# posboard.net
KiCad netlist of a schematic drawn in EAGLE
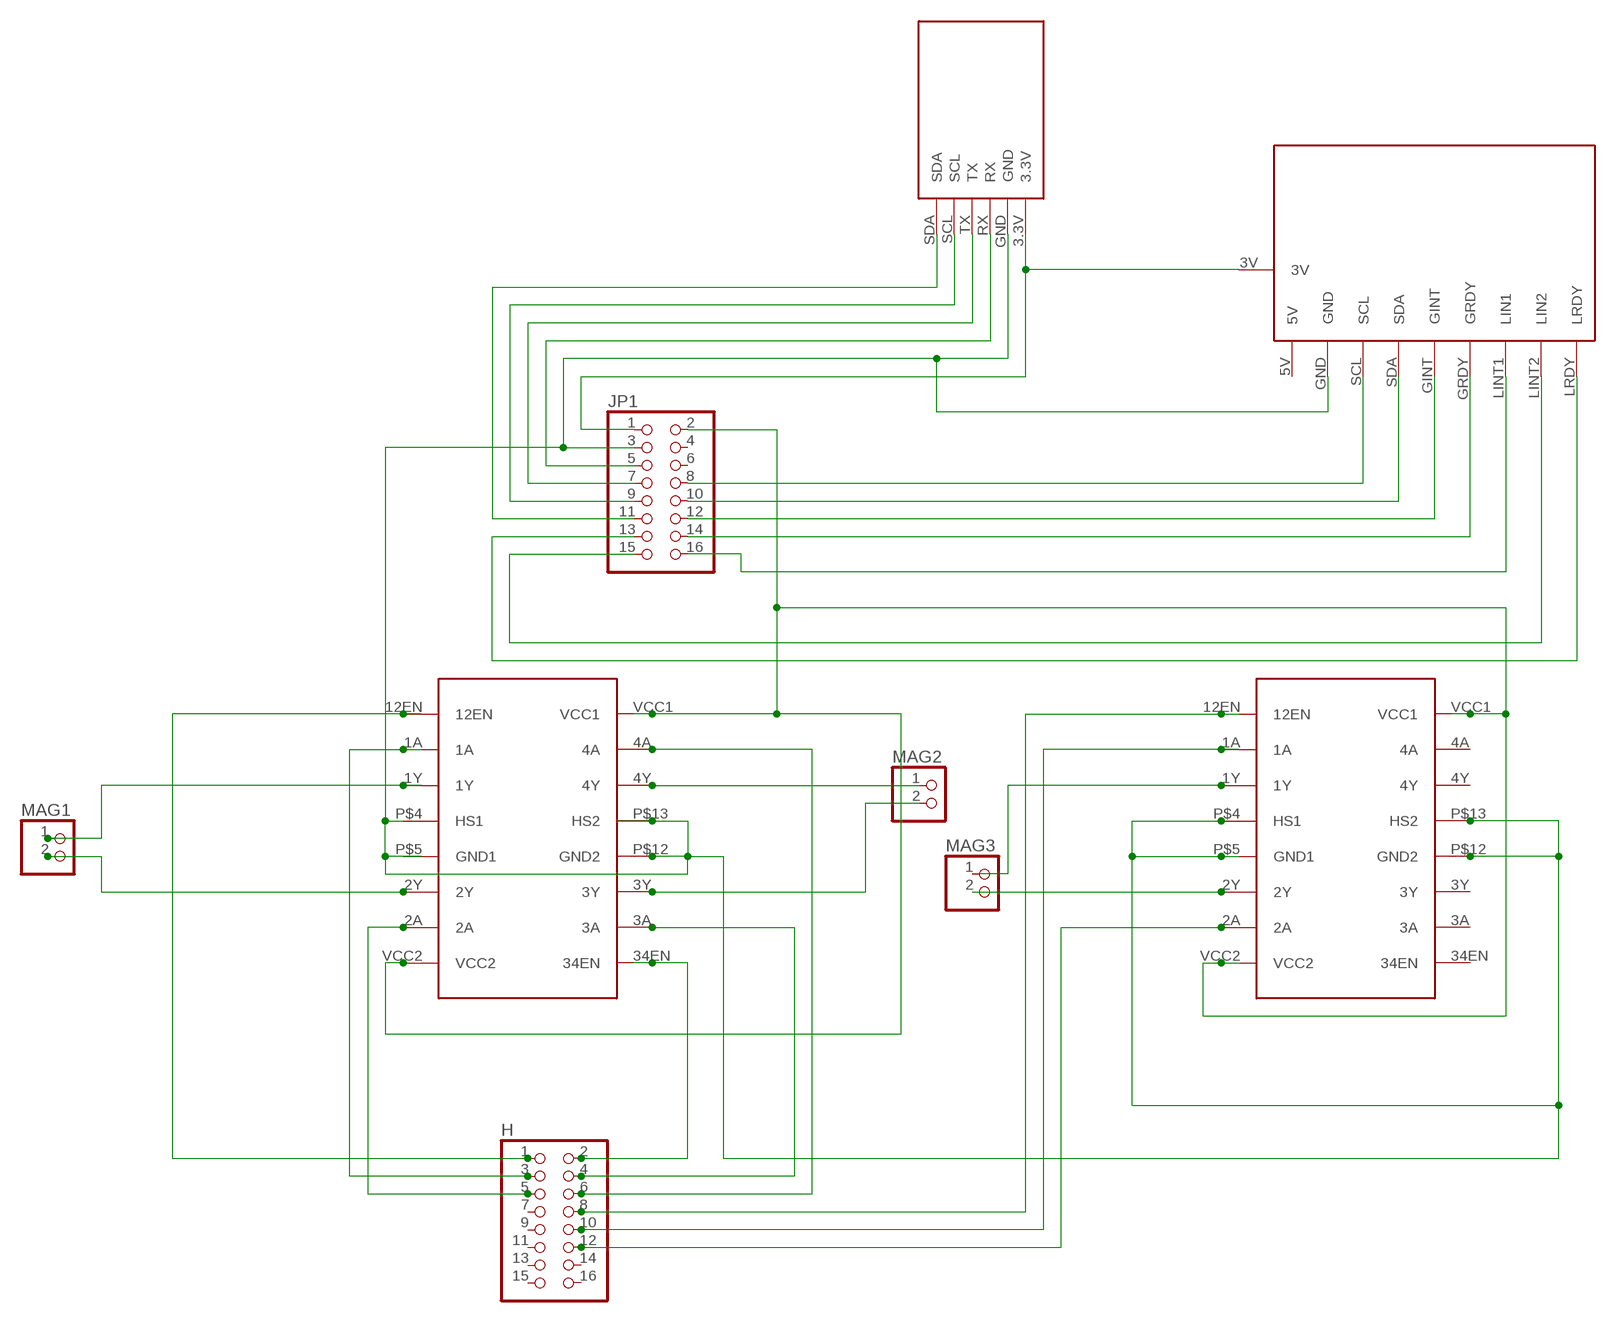
[diagram p0: schematic, sheet 1]

(export (version "E")
  (design (tool "Eeschema 10.0.6"))
  (components
    (comp (ref "H")
      (value "PINHD-2X8")
      (footprint "eagle-import:2X08")
      (libsource (lib "eagle-import") (part "PINHD-2X8"))
    )
    (comp (ref "JP1")
      (value "PINHD-2X8")
      (footprint "eagle-import:2X08")
      (libsource (lib "eagle-import") (part "PINHD-2X8"))
    )
    (comp (ref "MAG1")
      (value "PINHD-1X2")
      (footprint "eagle-import:1X02")
      (libsource (lib "eagle-import") (part "PINHD-1X2"))
    )
    (comp (ref "MAG2")
      (value "PINHD-1X2")
      (footprint "eagle-import:1X02")
      (libsource (lib "eagle-import") (part "PINHD-1X2"))
    )
    (comp (ref "MAG3")
      (value "PINHD-1X2")
      (footprint "eagle-import:1X02")
      (libsource (lib "eagle-import") (part "PINHD-1X2"))
    )
    (comp (ref "U$1")
      (value "GPS")
      (footprint "eagle-import:GPS")
      (libsource (lib "eagle-import") (part "GPS"))
    )
    (comp (ref "U$2")
      (value "IMU")
      (footprint "eagle-import:IMU")
      (libsource (lib "eagle-import") (part "IMU"))
    )
    (comp (ref "U$3")
      (value "HBRIDGE")
      (footprint "eagle-import:HBRIDGE")
      (libsource (lib "eagle-import") (part "HBRIDGE"))
    )
    (comp (ref "U$4")
      (value "HBRIDGE")
      (footprint "eagle-import:HBRIDGE")
      (libsource (lib "eagle-import") (part "HBRIDGE"))
    )
  )
  (nets
    (net (code "1") (name "Net-(H-Pad1)") (class "Default")
      (node (ref "H") (pin "1") (pinfunction "1_1") (pintype "passive"))
      (node (ref "U$3") (pin "12EN") (pinfunction "12EN_12EN") (pintype "bidirectional"))
    )
    (net (code "2") (name "Net-(H-Pad2)") (class "Default")
      (node (ref "H") (pin "2") (pinfunction "2_2") (pintype "passive"))
      (node (ref "U$3") (pin "34EN") (pinfunction "34EN_34EN") (pintype "bidirectional"))
    )
    (net (code "3") (name "Net-(H-Pad3)") (class "Default")
      (node (ref "H") (pin "3") (pinfunction "3_3") (pintype "passive"))
      (node (ref "U$3") (pin "1A") (pinfunction "1A_1A") (pintype "bidirectional"))
    )
    (net (code "4") (name "Net-(H-Pad4)") (class "Default")
      (node (ref "H") (pin "4") (pinfunction "4_4") (pintype "passive"))
      (node (ref "U$3") (pin "3A") (pinfunction "3A_3A") (pintype "bidirectional"))
    )
    (net (code "5") (name "Net-(H-Pad5)") (class "Default")
      (node (ref "H") (pin "5") (pinfunction "5_5") (pintype "passive"))
      (node (ref "U$3") (pin "2A") (pinfunction "2A_2A") (pintype "bidirectional"))
    )
    (net (code "6") (name "Net-(H-Pad6)") (class "Default")
      (node (ref "H") (pin "6") (pinfunction "6_6") (pintype "passive"))
      (node (ref "U$3") (pin "4A") (pinfunction "4A_4A") (pintype "bidirectional"))
    )
    (net (code "7") (name "Net-(H-Pad8)") (class "Default")
      (node (ref "H") (pin "8") (pinfunction "8_8") (pintype "passive"))
      (node (ref "U$4") (pin "12EN") (pinfunction "12EN_12EN") (pintype "bidirectional"))
    )
    (net (code "8") (name "Net-(H-Pad10)") (class "Default")
      (node (ref "H") (pin "10") (pinfunction "10_10") (pintype "passive"))
      (node (ref "U$4") (pin "1A") (pinfunction "1A_1A") (pintype "bidirectional"))
    )
    (net (code "9") (name "Net-(H-Pad12)") (class "Default")
      (node (ref "H") (pin "12") (pinfunction "12_12") (pintype "passive"))
      (node (ref "U$4") (pin "2A") (pinfunction "2A_2A") (pintype "bidirectional"))
    )
    (net (code "10") (name "Net-(JP1-Pad1)") (class "Default")
      (node (ref "JP1") (pin "1") (pinfunction "1_1") (pintype "passive"))
      (node (ref "U$1") (pin "3.3V") (pinfunction "3.3V_3.3V") (pintype "bidirectional"))
      (node (ref "U$2") (pin "3V") (pinfunction "3V_3V") (pintype "bidirectional"))
    )
    (net (code "11") (name "Net-(JP1-Pad2)") (class "Default")
      (node (ref "JP1") (pin "2") (pinfunction "2_2") (pintype "passive"))
      (node (ref "U$3") (pin "VCC1") (pinfunction "VCC1_VCC1") (pintype "bidirectional"))
      (node (ref "U$3") (pin "VCC2") (pinfunction "VCC2_VCC2") (pintype "bidirectional"))
      (node (ref "U$4") (pin "VCC1") (pinfunction "VCC1_VCC1") (pintype "bidirectional"))
      (node (ref "U$4") (pin "VCC2") (pinfunction "VCC2_VCC2") (pintype "bidirectional"))
    )
    (net (code "12") (name "Net-(JP1-Pad5)") (class "Default")
      (node (ref "JP1") (pin "5") (pinfunction "5_5") (pintype "passive"))
      (node (ref "U$1") (pin "RX") (pinfunction "RX_RX") (pintype "bidirectional"))
    )
    (net (code "13") (name "Net-(JP1-Pad7)") (class "Default")
      (node (ref "JP1") (pin "7") (pinfunction "7_7") (pintype "passive"))
      (node (ref "U$1") (pin "TX") (pinfunction "TX_TX") (pintype "bidirectional"))
    )
    (net (code "14") (name "Net-(JP1-Pad8)") (class "Default")
      (node (ref "JP1") (pin "8") (pinfunction "8_8") (pintype "passive"))
      (node (ref "U$2") (pin "SCL") (pinfunction "SCL_SCL") (pintype "bidirectional"))
    )
    (net (code "15") (name "Net-(JP1-Pad9)") (class "Default")
      (node (ref "JP1") (pin "9") (pinfunction "9_9") (pintype "passive"))
      (node (ref "U$1") (pin "SCL") (pinfunction "SCL_SCL") (pintype "bidirectional"))
    )
    (net (code "16") (name "Net-(JP1-Pad10)") (class "Default")
      (node (ref "JP1") (pin "10") (pinfunction "10_10") (pintype "passive"))
      (node (ref "U$2") (pin "SDA") (pinfunction "SDA_SDA") (pintype "bidirectional"))
    )
    (net (code "17") (name "Net-(JP1-Pad11)") (class "Default")
      (node (ref "JP1") (pin "11") (pinfunction "11_11") (pintype "passive"))
      (node (ref "U$1") (pin "SDA") (pinfunction "SDA_SDA") (pintype "bidirectional"))
    )
    (net (code "18") (name "Net-(JP1-Pad12)") (class "Default")
      (node (ref "JP1") (pin "12") (pinfunction "12_12") (pintype "passive"))
      (node (ref "U$2") (pin "GINT") (pinfunction "GINT_GINT") (pintype "bidirectional"))
    )
    (net (code "19") (name "Net-(JP1-Pad13)") (class "Default")
      (node (ref "JP1") (pin "13") (pinfunction "13_13") (pintype "passive"))
      (node (ref "U$2") (pin "LRDY") (pinfunction "LRDY_LRDY") (pintype "bidirectional"))
    )
    (net (code "20") (name "Net-(JP1-Pad14)") (class "Default")
      (node (ref "JP1") (pin "14") (pinfunction "14_14") (pintype "passive"))
      (node (ref "U$2") (pin "GRDY") (pinfunction "GRDY_GRDY") (pintype "bidirectional"))
    )
    (net (code "21") (name "Net-(MAG1-Pad1)") (class "Default")
      (node (ref "MAG1") (pin "1") (pinfunction "1_1") (pintype "passive"))
      (node (ref "U$3") (pin "1Y") (pinfunction "1Y_1Y") (pintype "bidirectional"))
    )
    (net (code "22") (name "Net-(MAG1-Pad2)") (class "Default")
      (node (ref "MAG1") (pin "2") (pinfunction "2_2") (pintype "passive"))
      (node (ref "U$3") (pin "2Y") (pinfunction "2Y_2Y") (pintype "bidirectional"))
    )
    (net (code "23") (name "Net-(MAG2-Pad1)") (class "Default")
      (node (ref "MAG2") (pin "1") (pinfunction "1_1") (pintype "passive"))
      (node (ref "U$3") (pin "4Y") (pinfunction "4Y_4Y") (pintype "bidirectional"))
    )
    (net (code "24") (name "Net-(MAG2-Pad2)") (class "Default")
      (node (ref "MAG2") (pin "2") (pinfunction "2_2") (pintype "passive"))
      (node (ref "U$3") (pin "3Y") (pinfunction "3Y_3Y") (pintype "bidirectional"))
    )
    (net (code "25") (name "Net-(MAG3-Pad1)") (class "Default")
      (node (ref "MAG3") (pin "1") (pinfunction "1_1") (pintype "passive"))
      (node (ref "U$4") (pin "1Y") (pinfunction "1Y_1Y") (pintype "bidirectional"))
    )
    (net (code "26") (name "Net-(MAG3-Pad2)") (class "Default")
      (node (ref "MAG3") (pin "2") (pinfunction "2_2") (pintype "passive"))
      (node (ref "U$4") (pin "2Y") (pinfunction "2Y_2Y") (pintype "bidirectional"))
    )
    (net (code "27") (name "Net-(U$2-LIN1)") (class "Default")
      (node (ref "JP1") (pin "16") (pinfunction "16_16") (pintype "passive"))
      (node (ref "U$2") (pin "LINT1") (pinfunction "LIN1_LINT1") (pintype "bidirectional"))
    )
    (net (code "28") (name "Net-(U$2-LIN2)") (class "Default")
      (node (ref "JP1") (pin "15") (pinfunction "15_15") (pintype "passive"))
      (node (ref "U$2") (pin "LINT2") (pinfunction "LIN2_LINT2") (pintype "bidirectional"))
    )
    (net (code "29") (name "Net-(U$3-GND2)") (class "Default")
      (node (ref "JP1") (pin "3") (pinfunction "3_3") (pintype "passive"))
      (node (ref "U$1") (pin "GND") (pinfunction "GND_GND") (pintype "bidirectional"))
      (node (ref "U$2") (pin "GND") (pinfunction "GND_GND") (pintype "bidirectional"))
      (node (ref "U$3") (pin "P$12") (pinfunction "GND2_P$12") (pintype "bidirectional"))
      (node (ref "U$3") (pin "P$13") (pinfunction "HS2_P$13") (pintype "bidirectional"))
      (node (ref "U$3") (pin "P$4") (pinfunction "HS1_P$4") (pintype "bidirectional"))
      (node (ref "U$4") (pin "P$12") (pinfunction "GND2_P$12") (pintype "bidirectional"))
      (node (ref "U$4") (pin "P$13") (pinfunction "HS2_P$13") (pintype "bidirectional"))
      (node (ref "U$4") (pin "P$4") (pinfunction "HS1_P$4") (pintype "bidirectional"))
      (node (ref "U$4") (pin "P$5") (pinfunction "GND1_P$5") (pintype "bidirectional"))
    )
    (net (code "30") (name "unconnected-(H-Pad7)") (class "Default")
      (node (ref "H") (pin "7") (pinfunction "7_7") (pintype "passive"))
    )
    (net (code "31") (name "unconnected-(H-Pad9)") (class "Default")
      (node (ref "H") (pin "9") (pinfunction "9_9") (pintype "passive"))
    )
    (net (code "32") (name "unconnected-(H-Pad11)") (class "Default")
      (node (ref "H") (pin "11") (pinfunction "11_11") (pintype "passive"))
    )
    (net (code "33") (name "unconnected-(H-Pad13)") (class "Default")
      (node (ref "H") (pin "13") (pinfunction "13_13") (pintype "passive"))
    )
    (net (code "34") (name "unconnected-(H-Pad14)") (class "Default")
      (node (ref "H") (pin "14") (pinfunction "14_14") (pintype "passive"))
    )
    (net (code "35") (name "unconnected-(H-Pad15)") (class "Default")
      (node (ref "H") (pin "15") (pinfunction "15_15") (pintype "passive"))
    )
    (net (code "36") (name "unconnected-(H-Pad16)") (class "Default")
      (node (ref "H") (pin "16") (pinfunction "16_16") (pintype "passive"))
    )
    (net (code "37") (name "unconnected-(JP1-Pad4)") (class "Default")
      (node (ref "JP1") (pin "4") (pinfunction "4_4") (pintype "passive"))
    )
    (net (code "38") (name "unconnected-(JP1-Pad6)") (class "Default")
      (node (ref "JP1") (pin "6") (pinfunction "6_6") (pintype "passive"))
    )
    (net (code "39") (name "unconnected-(U$2-Pad5V)") (class "Default")
      (node (ref "U$2") (pin "5V") (pinfunction "5V_5V") (pintype "bidirectional"))
    )
    (net (code "40") (name "unconnected-(U$3-GND1-PadP$5)") (class "Default")
      (node (ref "U$3") (pin "P$5") (pinfunction "GND1_P$5") (pintype "bidirectional"))
    )
    (net (code "41") (name "unconnected-(U$4-Pad3A)") (class "Default")
      (node (ref "U$4") (pin "3A") (pinfunction "3A_3A") (pintype "bidirectional"))
    )
    (net (code "42") (name "unconnected-(U$4-Pad3Y)") (class "Default")
      (node (ref "U$4") (pin "3Y") (pinfunction "3Y_3Y") (pintype "bidirectional"))
    )
    (net (code "43") (name "unconnected-(U$4-Pad4A)") (class "Default")
      (node (ref "U$4") (pin "4A") (pinfunction "4A_4A") (pintype "bidirectional"))
    )
    (net (code "44") (name "unconnected-(U$4-Pad4Y)") (class "Default")
      (node (ref "U$4") (pin "4Y") (pinfunction "4Y_4Y") (pintype "bidirectional"))
    )
    (net (code "45") (name "unconnected-(U$4-Pad34EN)") (class "Default")
      (node (ref "U$4") (pin "34EN") (pinfunction "34EN_34EN") (pintype "bidirectional"))
    )
  )
)
